# CAN-RAMPS.net
KiCad netlist of a schematic drawn in EAGLE
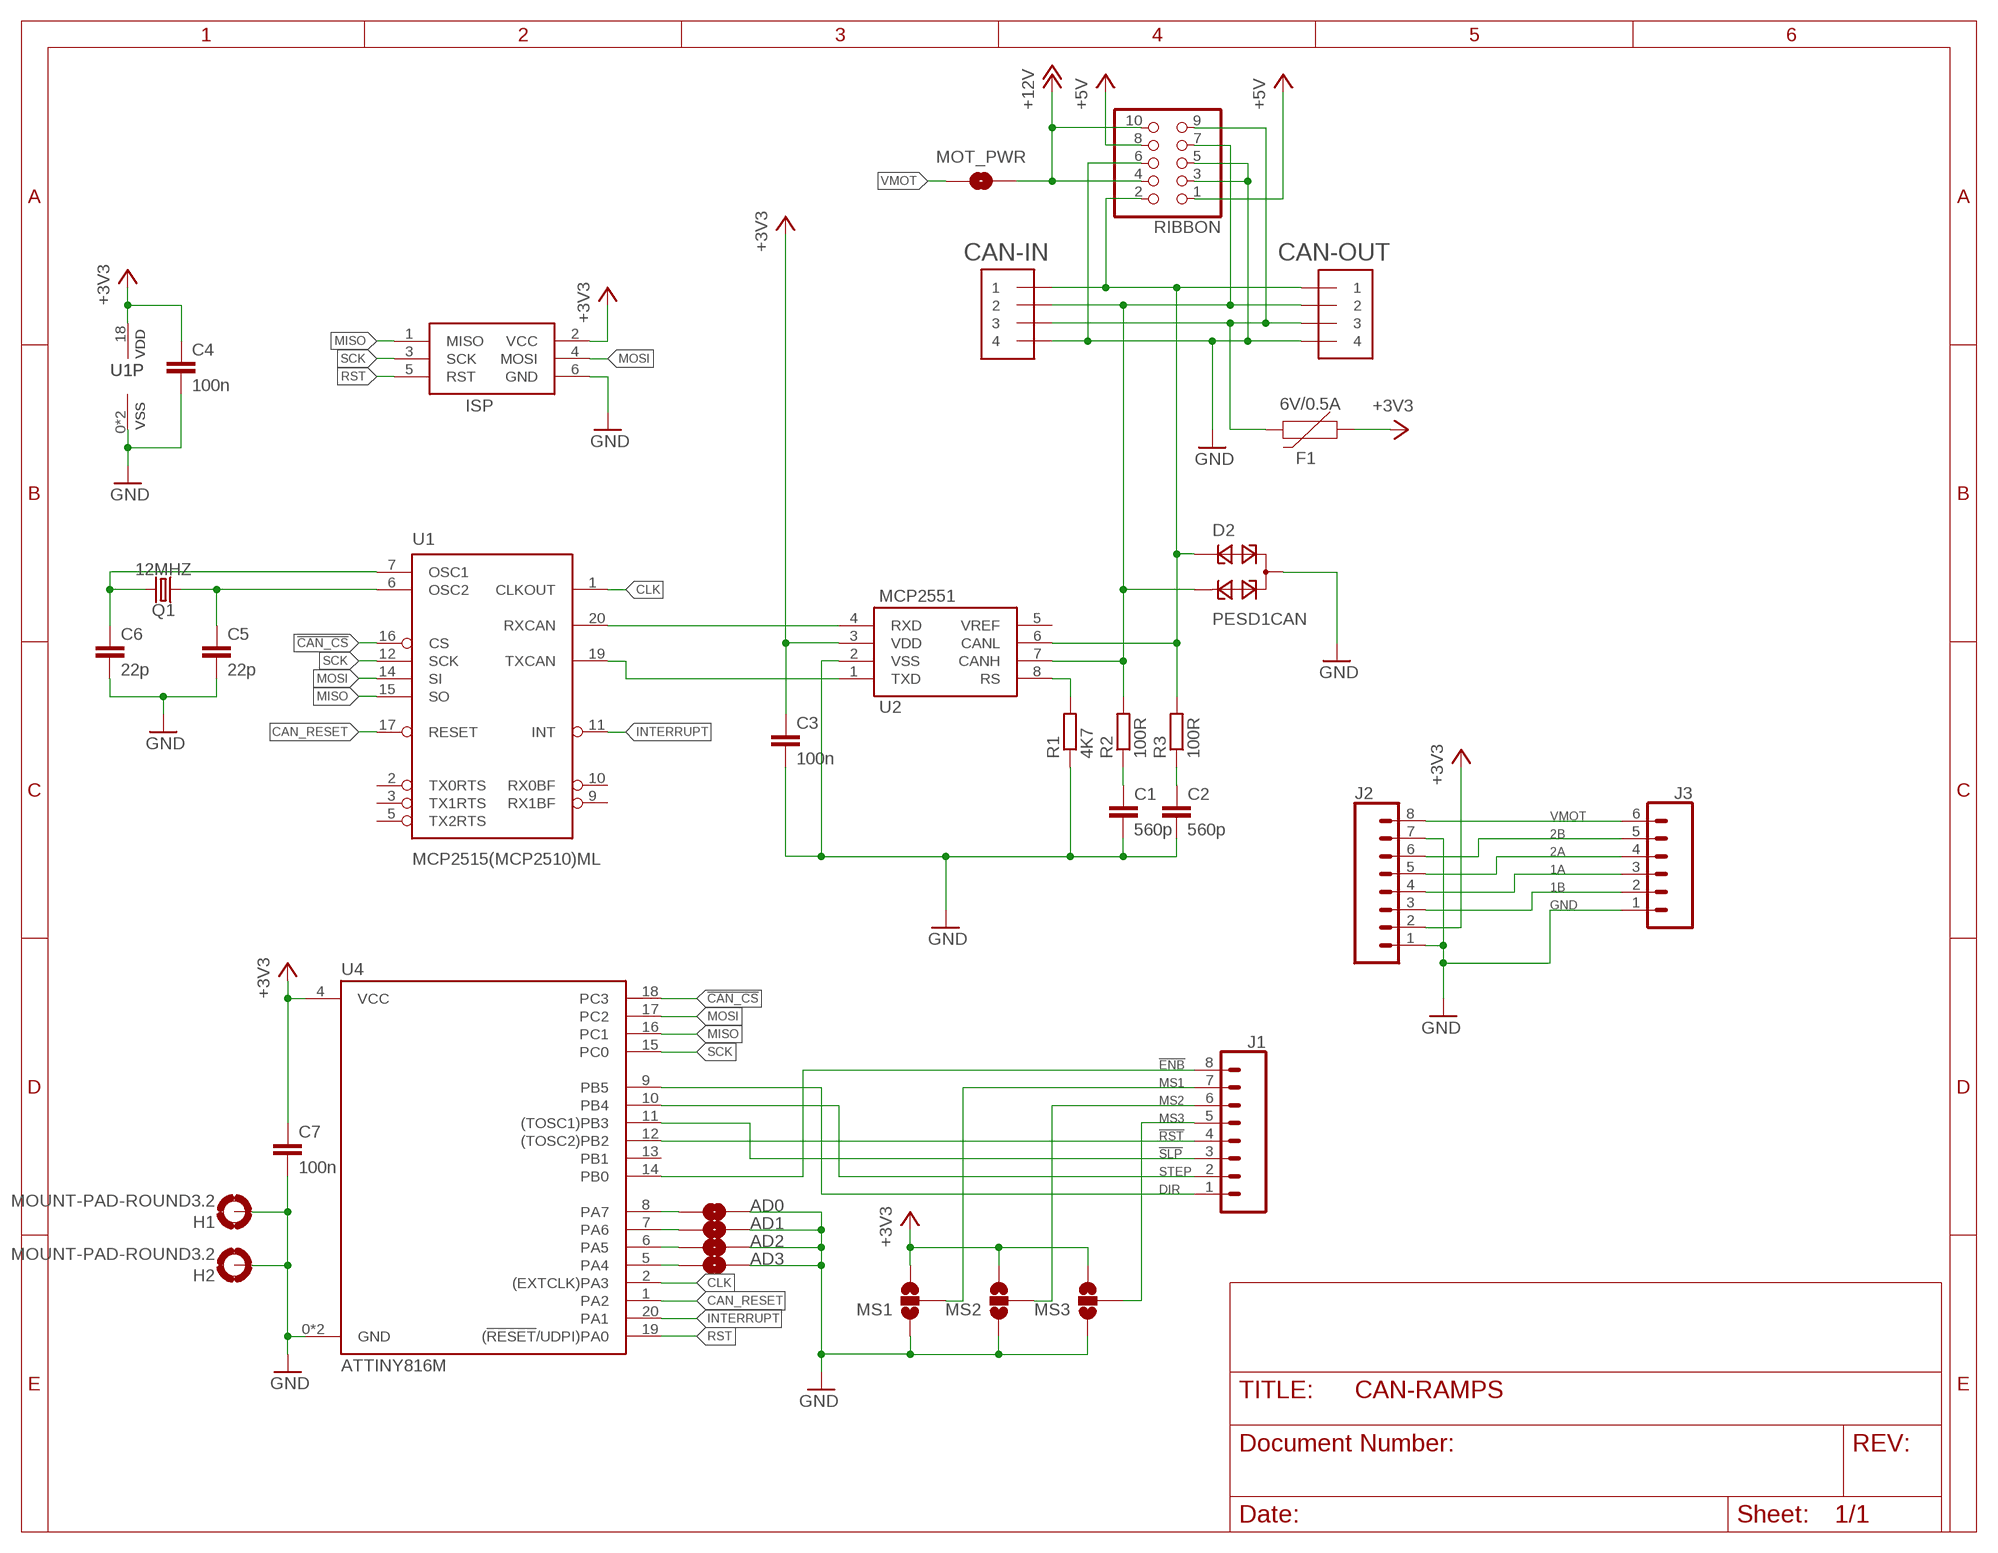
[diagram p0: schematic, sheet 1]

(export (version "E")
  (design (tool "Eeschema 10.0.6"))
  (components
    (comp (ref "AD0")
      (value "JUMPER-SMT_2_NO_SILK")
      (footprint "eagle-import:SMT-JUMPER_2_NO_SILK")
      (libsource (lib "eagle-import") (part "JUMPER-SMT_2_NO_SILK"))
    )
    (comp (ref "AD1")
      (value "JUMPER-SMT_2_NO_SILK")
      (footprint "eagle-import:SMT-JUMPER_2_NO_SILK")
      (libsource (lib "eagle-import") (part "JUMPER-SMT_2_NO_SILK"))
    )
    (comp (ref "AD2")
      (value "JUMPER-SMT_2_NO_SILK")
      (footprint "eagle-import:SMT-JUMPER_2_NO_SILK")
      (libsource (lib "eagle-import") (part "JUMPER-SMT_2_NO_SILK"))
    )
    (comp (ref "AD3")
      (value "JUMPER-SMT_2_NO_SILK")
      (footprint "eagle-import:SMT-JUMPER_2_NO_SILK")
      (libsource (lib "eagle-import") (part "JUMPER-SMT_2_NO_SILK"))
    )
    (comp (ref "C1")
      (value "560p")
      (footprint "eagle-import:C0603")
      (libsource (lib "eagle-import") (part "C-EUC0603"))
    )
    (comp (ref "C2")
      (value "560p")
      (footprint "eagle-import:C0603")
      (libsource (lib "eagle-import") (part "C-EUC0603"))
    )
    (comp (ref "C3")
      (value "100n")
      (footprint "eagle-import:C0603")
      (libsource (lib "eagle-import") (part "C-EUC0603"))
    )
    (comp (ref "C4")
      (value "100n")
      (footprint "eagle-import:C0603")
      (libsource (lib "eagle-import") (part "C-EUC0603"))
    )
    (comp (ref "C5")
      (value "22p")
      (footprint "eagle-import:C0603")
      (libsource (lib "eagle-import") (part "C-EUC0603"))
    )
    (comp (ref "C6")
      (value "22p")
      (footprint "eagle-import:C0603")
      (libsource (lib "eagle-import") (part "C-EUC0603"))
    )
    (comp (ref "C7")
      (value "100n")
      (footprint "eagle-import:C0603")
      (libsource (lib "eagle-import") (part "C-EUC0603"))
    )
    (comp (ref "CAN-IN")
      (value "STRAWSON_EAGLE_LIB_JST_SH_4")
      (footprint "eagle-import:STRAWSON_EAGLE_LIB_JST_SH_4_SMD")
      (libsource (lib "eagle-import") (part "STRAWSON_EAGLE_LIB_JST_SH_4"))
    )
    (comp (ref "CAN-OUT")
      (value "STRAWSON_EAGLE_LIB_JST_SH_4")
      (footprint "eagle-import:STRAWSON_EAGLE_LIB_JST_SH_4_SMD")
      (libsource (lib "eagle-import") (part "STRAWSON_EAGLE_LIB_JST_SH_4"))
    )
    (comp (ref "D2")
      (value "PESD1CAN")
      (footprint "eagle-import:SOT23")
      (libsource (lib "eagle-import") (part "PESD1CAN"))
    )
    (comp (ref "F1")
      (value "6V/0.5A")
      (footprint "eagle-import:1206")
      (libsource (lib "eagle-import") (part "PPTC_HALF-AMP"))
    )
    (comp (ref "H1")
      (value "MOUNT-PAD-ROUND3.2")
      (footprint "eagle-import:3,2-PAD")
      (libsource (lib "eagle-import") (part "MOUNT-PAD-ROUND3.2"))
    )
    (comp (ref "H2")
      (value "MOUNT-PAD-ROUND3.2")
      (footprint "eagle-import:3,2-PAD")
      (libsource (lib "eagle-import") (part "MOUNT-PAD-ROUND3.2"))
    )
    (comp (ref "ISP")
      (value "AVRISP-6")
      (footprint "eagle-import:AVRISP")
      (libsource (lib "eagle-import") (part "AVRISP-6"))
    )
    (comp (ref "J1")
      (value "CONN_08LOCK")
      (footprint "eagle-import:1X08_LOCK")
      (libsource (lib "eagle-import") (part "CONN_08LOCK"))
    )
    (comp (ref "J2")
      (value "CONN_08LOCK")
      (footprint "eagle-import:1X08_LOCK")
      (libsource (lib "eagle-import") (part "CONN_08LOCK"))
    )
    (comp (ref "J3")
      (value "CONN_06LOCK_LONGPADS")
      (footprint "eagle-import:1X06_LOCK_LONGPADS")
      (libsource (lib "eagle-import") (part "CONN_06LOCK_LONGPADS"))
    )
    (comp (ref "MOT_PWR")
      (value "JUMPER-SMT_2_NO_SILK")
      (footprint "eagle-import:SMT-JUMPER_2_NO_SILK")
      (libsource (lib "eagle-import") (part "JUMPER-SMT_2_NO_SILK"))
    )
    (comp (ref "MS1")
      (value "JUMPER-SMT_3_NO_SILK")
      (footprint "eagle-import:SMT-JUMPER_3_NO_SILK")
      (libsource (lib "eagle-import") (part "JUMPER-SMT_3_NO_SILK"))
    )
    (comp (ref "MS2")
      (value "JUMPER-SMT_3_NO_SILK")
      (footprint "eagle-import:SMT-JUMPER_3_NO_SILK")
      (libsource (lib "eagle-import") (part "JUMPER-SMT_3_NO_SILK"))
    )
    (comp (ref "MS3")
      (value "JUMPER-SMT_3_NO_SILK")
      (footprint "eagle-import:SMT-JUMPER_3_NO_SILK")
      (libsource (lib "eagle-import") (part "JUMPER-SMT_3_NO_SILK"))
    )
    (comp (ref "Q1")
      (value "12MHZ")
      (footprint "eagle-import:CRYSTAL-SMD-3.2X1.5MM")
      (libsource (lib "eagle-import") (part "CRYSTALSMD-3.2X1.5"))
    )
    (comp (ref "R1")
      (value "4K7")
      (footprint "eagle-import:R0603")
      (libsource (lib "eagle-import") (part "R-EU_R0603"))
    )
    (comp (ref "R2")
      (value "100R")
      (footprint "eagle-import:R0603")
      (libsource (lib "eagle-import") (part "R-EU_R0603"))
    )
    (comp (ref "R3")
      (value "100R")
      (footprint "eagle-import:R0603")
      (libsource (lib "eagle-import") (part "R-EU_R0603"))
    )
    (comp (ref "RIBBON")
      (value "PINHD-2X5_2.54-SMD")
      (footprint "eagle-import:2X05SMD")
      (libsource (lib "eagle-import") (part "PINHD-2X5_2.54-SMD"))
    )
    (comp (ref "U1")
      (value "MCP2515(MCP2510)ML")
      (footprint "eagle-import:QFN20")
      (libsource (lib "eagle-import") (part "MCP2515(MCP2510)ML"))
    )
    (comp (ref "U2")
      (value "MCP2551")
      (footprint "eagle-import:SO08")
      (libsource (lib "eagle-import") (part "MCP2551"))
    )
    (comp (ref "U4")
      (value "ATTINY816M")
      (footprint "eagle-import:QFN20")
      (libsource (lib "eagle-import") (part "ATTINY816M"))
    )
  )
  (nets
    (net (code "1") (name "+3V3") (class "Default")
      (node (ref "C3") (pin "1") (pinfunction "1_1") (pintype "passive"))
      (node (ref "C4") (pin "1") (pinfunction "1_1") (pintype "passive"))
      (node (ref "C7") (pin "1") (pinfunction "1_1") (pintype "passive"))
      (node (ref "F1") (pin "1") (pinfunction "1_1") (pintype "bidirectional"))
      (node (ref "ISP") (pin "2") (pinfunction "VCC_2") (pintype "power_in"))
      (node (ref "J2") (pin "2") (pinfunction "2_2") (pintype "passive"))
      (node (ref "MS1") (pin "3") (pinfunction "3_3") (pintype "passive"))
      (node (ref "MS2") (pin "3") (pinfunction "3_3") (pintype "passive"))
      (node (ref "MS3") (pin "3") (pinfunction "3_3") (pintype "passive"))
      (node (ref "U1") (pin "18") (pinfunction "VDD_18") (pintype "power_in"))
      (node (ref "U2") (pin "3") (pinfunction "VDD_3") (pintype "bidirectional"))
      (node (ref "U4") (pin "4") (pinfunction "VCC_4") (pintype "bidirectional"))
    )
    (net (code "2") (name "+5V") (class "Default")
      (node (ref "RIBBON") (pin "1") (pinfunction "1_1") (pintype "passive"))
      (node (ref "RIBBON") (pin "8") (pinfunction "8_8") (pintype "passive"))
    )
    (net (code "3") (name "+12V") (class "Default")
      (node (ref "MOT_PWR") (pin "2") (pinfunction "2_2") (pintype "passive"))
      (node (ref "RIBBON") (pin "10") (pinfunction "10_10") (pintype "passive"))
      (node (ref "RIBBON") (pin "4") (pinfunction "4_4") (pintype "passive"))
    )
    (net (code "4") (name "/1A") (class "Default")
      (node (ref "J2") (pin "4") (pinfunction "4_4") (pintype "passive"))
      (node (ref "J3") (pin "3") (pinfunction "3_3") (pintype "passive"))
    )
    (net (code "5") (name "/1B") (class "Default")
      (node (ref "J2") (pin "3") (pinfunction "3_3") (pintype "passive"))
      (node (ref "J3") (pin "2") (pinfunction "2_2") (pintype "passive"))
    )
    (net (code "6") (name "/2A") (class "Default")
      (node (ref "J2") (pin "5") (pinfunction "5_5") (pintype "passive"))
      (node (ref "J3") (pin "4") (pinfunction "4_4") (pintype "passive"))
    )
    (net (code "7") (name "/2B") (class "Default")
      (node (ref "J2") (pin "6") (pinfunction "6_6") (pintype "passive"))
      (node (ref "J3") (pin "5") (pinfunction "5_5") (pintype "passive"))
    )
    (net (code "8") (name "/DIR") (class "Default")
      (node (ref "J1") (pin "1") (pinfunction "1_1") (pintype "passive"))
      (node (ref "U4") (pin "9") (pinfunction "PB5_9") (pintype "bidirectional"))
    )
    (net (code "9") (name "/MS1") (class "Default")
      (node (ref "J1") (pin "7") (pinfunction "7_7") (pintype "passive"))
      (node (ref "MS1") (pin "2") (pinfunction "2_2") (pintype "passive"))
    )
    (net (code "10") (name "/MS2") (class "Default")
      (node (ref "J1") (pin "6") (pinfunction "6_6") (pintype "passive"))
      (node (ref "MS2") (pin "2") (pinfunction "2_2") (pintype "passive"))
    )
    (net (code "11") (name "/MS3") (class "Default")
      (node (ref "J1") (pin "5") (pinfunction "5_5") (pintype "passive"))
      (node (ref "MS3") (pin "2") (pinfunction "2_2") (pintype "passive"))
    )
    (net (code "12") (name "/STEP") (class "Default")
      (node (ref "J1") (pin "2") (pinfunction "2_2") (pintype "passive"))
      (node (ref "U4") (pin "10") (pinfunction "PB4_10") (pintype "bidirectional"))
    )
    (net (code "13") (name "/~{CAN_CS}") (class "Default")
      (node (ref "U1") (pin "16") (pinfunction "CS_16") (pintype "input"))
      (node (ref "U4") (pin "18") (pinfunction "PC3_18") (pintype "bidirectional"))
    )
    (net (code "14") (name "/~{ENB}") (class "Default")
      (node (ref "J1") (pin "8") (pinfunction "8_8") (pintype "passive"))
      (node (ref "U4") (pin "14") (pinfunction "PB0_14") (pintype "bidirectional"))
    )
    (net (code "15") (name "/~{RST}") (class "Default")
      (node (ref "J1") (pin "4") (pinfunction "4_4") (pintype "passive"))
      (node (ref "U4") (pin "12") (pinfunction "(TOSC2)PB2_12") (pintype "bidirectional"))
    )
    (net (code "16") (name "/~{SLP}") (class "Default")
      (node (ref "J1") (pin "3") (pinfunction "3_3") (pintype "passive"))
      (node (ref "U4") (pin "11") (pinfunction "(TOSC1)PB3_11") (pintype "bidirectional"))
    )
    (net (code "17") (name "CAN_RESET") (class "Default")
      (node (ref "U1") (pin "17") (pinfunction "RESET_17") (pintype "input"))
      (node (ref "U4") (pin "1") (pinfunction "PA2_1") (pintype "bidirectional"))
    )
    (net (code "18") (name "CLK") (class "Default")
      (node (ref "U1") (pin "1") (pinfunction "CLKOUT_1") (pintype "output"))
      (node (ref "U4") (pin "2") (pinfunction "(EXTCLK)PA3_2") (pintype "bidirectional"))
    )
    (net (code "19") (name "GND") (class "Default")
      (node (ref "AD0") (pin "2") (pinfunction "2_2") (pintype "passive"))
      (node (ref "AD1") (pin "2") (pinfunction "2_2") (pintype "passive"))
      (node (ref "AD2") (pin "2") (pinfunction "2_2") (pintype "passive"))
      (node (ref "AD3") (pin "2") (pinfunction "2_2") (pintype "passive"))
      (node (ref "C1") (pin "2") (pinfunction "2_2") (pintype "passive"))
      (node (ref "C2") (pin "2") (pinfunction "2_2") (pintype "passive"))
      (node (ref "C3") (pin "2") (pinfunction "2_2") (pintype "passive"))
      (node (ref "C4") (pin "2") (pinfunction "2_2") (pintype "passive"))
      (node (ref "C5") (pin "2") (pinfunction "2_2") (pintype "passive"))
      (node (ref "C6") (pin "2") (pinfunction "2_2") (pintype "passive"))
      (node (ref "C7") (pin "2") (pinfunction "2_2") (pintype "passive"))
      (node (ref "CAN-IN") (pin "4") (pinfunction "4_4") (pintype "bidirectional"))
      (node (ref "CAN-OUT") (pin "4") (pinfunction "4_4") (pintype "bidirectional"))
      (node (ref "D2") (pin "3") (pinfunction "3_3") (pintype "passive"))
      (node (ref "H1") (pin "B3,2") (pinfunction "MOUNT_B3,2") (pintype "passive"))
      (node (ref "H2") (pin "B3,2") (pinfunction "MOUNT_B3,2") (pintype "passive"))
      (node (ref "ISP") (pin "6") (pinfunction "GND_6") (pintype "power_in"))
      (node (ref "J2") (pin "1") (pinfunction "1_1") (pintype "passive"))
      (node (ref "J2") (pin "7") (pinfunction "7_7") (pintype "passive"))
      (node (ref "J3") (pin "1") (pinfunction "1_1") (pintype "passive"))
      (node (ref "MS1") (pin "1") (pinfunction "1_1") (pintype "passive"))
      (node (ref "MS2") (pin "1") (pinfunction "1_1") (pintype "passive"))
      (node (ref "MS3") (pin "1") (pinfunction "1_1") (pintype "passive"))
      (node (ref "R1") (pin "1") (pinfunction "1_1") (pintype "passive"))
      (node (ref "RIBBON") (pin "3") (pinfunction "3_3") (pintype "passive"))
      (node (ref "RIBBON") (pin "5") (pinfunction "5_5") (pintype "passive"))
      (node (ref "RIBBON") (pin "6") (pinfunction "6_6") (pintype "passive"))
      (node (ref "U1") (pin "0") (pinfunction "VSS_0") (pintype "power_in"))
      (node (ref "U1") (pin "8") (pinfunction "VSS_8") (pintype "power_in"))
      (node (ref "U2") (pin "2") (pinfunction "VSS_2") (pintype "bidirectional"))
      (node (ref "U4") (pin "0") (pinfunction "GND_0") (pintype "bidirectional"))
      (node (ref "U4") (pin "3") (pinfunction "GND_3") (pintype "bidirectional"))
    )
    (net (code "20") (name "INTERRUPT") (class "Default")
      (node (ref "U1") (pin "11") (pinfunction "INT_11") (pintype "output"))
      (node (ref "U4") (pin "20") (pinfunction "PA1_20") (pintype "bidirectional"))
    )
    (net (code "21") (name "MISO") (class "Default")
      (node (ref "ISP") (pin "1") (pinfunction "MISO_1") (pintype "input"))
      (node (ref "U1") (pin "15") (pinfunction "SO_15") (pintype "output"))
      (node (ref "U4") (pin "16") (pinfunction "PC1_16") (pintype "bidirectional"))
    )
    (net (code "22") (name "MOSI") (class "Default")
      (node (ref "ISP") (pin "4") (pinfunction "MOSI_4") (pintype "output"))
      (node (ref "U1") (pin "14") (pinfunction "SI_14") (pintype "input"))
      (node (ref "U4") (pin "17") (pinfunction "PC2_17") (pintype "bidirectional"))
    )
    (net (code "23") (name "Net-(C1-Pad1)") (class "Default")
      (node (ref "C1") (pin "1") (pinfunction "1_1") (pintype "passive"))
      (node (ref "R2") (pin "1") (pinfunction "1_1") (pintype "passive"))
    )
    (net (code "24") (name "Net-(C2-Pad1)") (class "Default")
      (node (ref "C2") (pin "1") (pinfunction "1_1") (pintype "passive"))
      (node (ref "R3") (pin "1") (pinfunction "1_1") (pintype "passive"))
    )
    (net (code "25") (name "Net-(CAN-IN-Pad3)") (class "Default")
      (node (ref "CAN-IN") (pin "3") (pinfunction "3_3") (pintype "bidirectional"))
      (node (ref "CAN-OUT") (pin "3") (pinfunction "3_3") (pintype "bidirectional"))
      (node (ref "F1") (pin "2") (pinfunction "2_2") (pintype "bidirectional"))
      (node (ref "RIBBON") (pin "9") (pinfunction "9_9") (pintype "passive"))
    )
    (net (code "26") (name "Net-(Q1-1)") (class "Default")
      (node (ref "C5") (pin "1") (pinfunction "1_1") (pintype "passive"))
      (node (ref "Q1") (pin "P$1") (pinfunction "1_P$1") (pintype "passive"))
      (node (ref "U1") (pin "6") (pinfunction "OSC2_6") (pintype "output"))
    )
    (net (code "27") (name "Net-(Q1-2)") (class "Default")
      (node (ref "C6") (pin "1") (pinfunction "1_1") (pintype "passive"))
      (node (ref "Q1") (pin "P$2") (pinfunction "2_P$2") (pintype "passive"))
      (node (ref "U1") (pin "7") (pinfunction "OSC1_7") (pintype "input"))
    )
    (net (code "28") (name "Net-(U1A-RXCAN)") (class "Default")
      (node (ref "U1") (pin "20") (pinfunction "RXCAN_20") (pintype "input"))
      (node (ref "U2") (pin "4") (pinfunction "RXD_4") (pintype "bidirectional"))
    )
    (net (code "29") (name "Net-(U1A-TXCAN)") (class "Default")
      (node (ref "U1") (pin "19") (pinfunction "TXCAN_19") (pintype "output"))
      (node (ref "U2") (pin "1") (pinfunction "TXD_1") (pintype "bidirectional"))
    )
    (net (code "30") (name "Net-(U2-CANH)") (class "Default")
      (node (ref "CAN-IN") (pin "2") (pinfunction "2_2") (pintype "bidirectional"))
      (node (ref "CAN-OUT") (pin "2") (pinfunction "2_2") (pintype "bidirectional"))
      (node (ref "D2") (pin "2") (pinfunction "2_2") (pintype "passive"))
      (node (ref "R2") (pin "2") (pinfunction "2_2") (pintype "passive"))
      (node (ref "RIBBON") (pin "7") (pinfunction "7_7") (pintype "passive"))
      (node (ref "U2") (pin "7") (pinfunction "CANH_7") (pintype "bidirectional"))
    )
    (net (code "31") (name "Net-(U2-CANL)") (class "Default")
      (node (ref "CAN-IN") (pin "1") (pinfunction "1_1") (pintype "bidirectional"))
      (node (ref "CAN-OUT") (pin "1") (pinfunction "1_1") (pintype "bidirectional"))
      (node (ref "D2") (pin "1") (pinfunction "1_1") (pintype "passive"))
      (node (ref "R3") (pin "2") (pinfunction "2_2") (pintype "passive"))
      (node (ref "RIBBON") (pin "2") (pinfunction "2_2") (pintype "passive"))
      (node (ref "U2") (pin "6") (pinfunction "CANL_6") (pintype "bidirectional"))
    )
    (net (code "32") (name "Net-(U2-RS)") (class "Default")
      (node (ref "R1") (pin "2") (pinfunction "2_2") (pintype "passive"))
      (node (ref "U2") (pin "8") (pinfunction "RS_8") (pintype "bidirectional"))
    )
    (net (code "33") (name "Net-(U4-PA4)") (class "Default")
      (node (ref "AD3") (pin "1") (pinfunction "1_1") (pintype "passive"))
      (node (ref "U4") (pin "5") (pinfunction "PA4_5") (pintype "bidirectional"))
    )
    (net (code "34") (name "Net-(U4-PA5)") (class "Default")
      (node (ref "AD2") (pin "1") (pinfunction "1_1") (pintype "passive"))
      (node (ref "U4") (pin "6") (pinfunction "PA5_6") (pintype "bidirectional"))
    )
    (net (code "35") (name "Net-(U4-PA6)") (class "Default")
      (node (ref "AD1") (pin "1") (pinfunction "1_1") (pintype "passive"))
      (node (ref "U4") (pin "7") (pinfunction "PA6_7") (pintype "bidirectional"))
    )
    (net (code "36") (name "Net-(U4-PA7)") (class "Default")
      (node (ref "AD0") (pin "1") (pinfunction "1_1") (pintype "passive"))
      (node (ref "U4") (pin "8") (pinfunction "PA7_8") (pintype "bidirectional"))
    )
    (net (code "37") (name "RST") (class "Default")
      (node (ref "ISP") (pin "5") (pinfunction "RST_5") (pintype "output"))
      (node (ref "U4") (pin "19") (pinfunction "(~{RESET}/UDPI)PA0_19") (pintype "bidirectional"))
    )
    (net (code "38") (name "SCK") (class "Default")
      (node (ref "ISP") (pin "3") (pinfunction "SCK_3") (pintype "output"))
      (node (ref "U1") (pin "12") (pinfunction "SCK_12") (pintype "input"))
      (node (ref "U4") (pin "15") (pinfunction "PC0_15") (pintype "bidirectional"))
    )
    (net (code "39") (name "VMOT") (class "Default")
      (node (ref "J2") (pin "8") (pinfunction "8_8") (pintype "passive"))
      (node (ref "J3") (pin "6") (pinfunction "6_6") (pintype "passive"))
      (node (ref "MOT_PWR") (pin "1") (pinfunction "1_1") (pintype "passive"))
    )
    (net (code "40") (name "unconnected-(U1A-RX0BF-Pad10)") (class "Default")
      (node (ref "U1") (pin "10") (pinfunction "RX0BF_10") (pintype "output"))
    )
    (net (code "41") (name "unconnected-(U1A-RX1BF-Pad9)") (class "Default")
      (node (ref "U1") (pin "9") (pinfunction "RX1BF_9") (pintype "output"))
    )
    (net (code "42") (name "unconnected-(U1A-TX0RTS-Pad2)") (class "Default")
      (node (ref "U1") (pin "2") (pinfunction "TX0RTS_2") (pintype "input"))
    )
    (net (code "43") (name "unconnected-(U1A-TX1RTS-Pad3)") (class "Default")
      (node (ref "U1") (pin "3") (pinfunction "TX1RTS_3") (pintype "input"))
    )
    (net (code "44") (name "unconnected-(U1A-TX2RTS-Pad5)") (class "Default")
      (node (ref "U1") (pin "5") (pinfunction "TX2RTS_5") (pintype "input"))
    )
    (net (code "45") (name "unconnected-(U2-VREF-Pad5)") (class "Default")
      (node (ref "U2") (pin "5") (pinfunction "VREF_5") (pintype "bidirectional"))
    )
    (net (code "46") (name "unconnected-(U4-PB1-Pad13)") (class "Default")
      (node (ref "U4") (pin "13") (pinfunction "PB1_13") (pintype "bidirectional"))
    )
  )
)
